# Skaarhoj_VU_board_with_LEDs.net
KiCad netlist of a schematic drawn in EAGLE
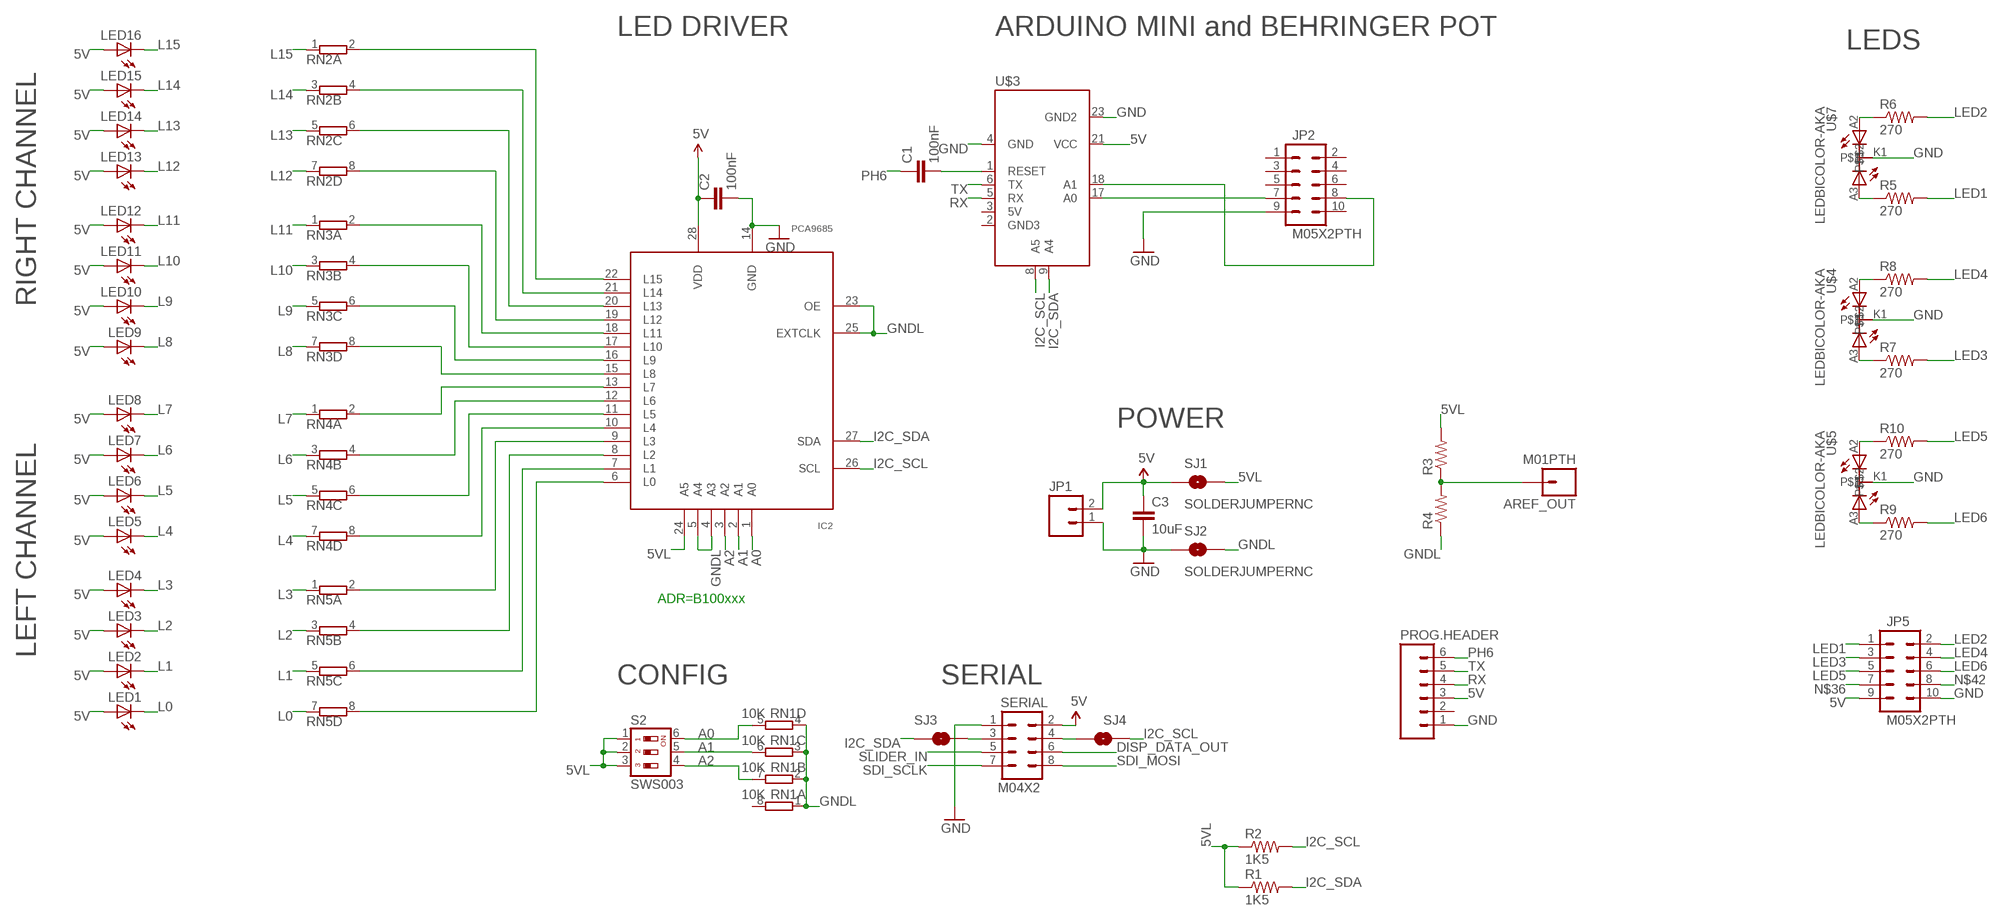
[diagram p0: schematic, sheet 1]

(export (version "E")
  (design (tool "Eeschema 10.0.6"))
  (components
    (comp (ref "AREF_OUT")
      (value "M01PTH")
      (footprint "eagle-import:1X01")
      (libsource (lib "eagle-import") (part "M01PTH"))
    )
    (comp (ref "C1")
      (value "100nF")
      (footprint "eagle-import:0603-CAP")
      (libsource (lib "eagle-import") (part "CAP0603-CAP"))
    )
    (comp (ref "C2")
      (value "100nF")
      (footprint "eagle-import:0603-CAP")
      (libsource (lib "eagle-import") (part "CAP0603-CAP"))
    )
    (comp (ref "C3")
      (value "10uF")
      (footprint "eagle-import:0805")
      (libsource (lib "eagle-import") (part "CAP0805"))
    )
    (comp (ref "IC2")
      (value "PCA9685")
      (footprint "eagle-import:TSSOP28")
      (libsource (lib "eagle-import") (part "PCA9685"))
    )
    (comp (ref "JP1")
      (value "M02PTH")
      (footprint "eagle-import:1X02")
      (libsource (lib "eagle-import") (part "M02PTH"))
    )
    (comp (ref "JP2")
      (value "M05X2PTH")
      (footprint "eagle-import:AVR_ICSP")
      (libsource (lib "eagle-import") (part "M05X2PTH"))
    )
    (comp (ref "JP5")
      (value "M05X2PTH")
      (footprint "eagle-import:AVR_ICSP")
      (libsource (lib "eagle-import") (part "M05X2PTH"))
    )
    (comp (ref "LED1")
      (value "LED3MM")
      (footprint "eagle-import:LED3MM")
      (libsource (lib "eagle-import") (part "LED3MM"))
    )
    (comp (ref "LED2")
      (value "LED3MM")
      (footprint "eagle-import:LED3MM")
      (libsource (lib "eagle-import") (part "LED3MM"))
    )
    (comp (ref "LED3")
      (value "LED3MM")
      (footprint "eagle-import:LED3MM")
      (libsource (lib "eagle-import") (part "LED3MM"))
    )
    (comp (ref "LED4")
      (value "LED3MM")
      (footprint "eagle-import:LED3MM")
      (libsource (lib "eagle-import") (part "LED3MM"))
    )
    (comp (ref "LED5")
      (value "LED3MM")
      (footprint "eagle-import:LED3MM")
      (libsource (lib "eagle-import") (part "LED3MM"))
    )
    (comp (ref "LED6")
      (value "LED3MM")
      (footprint "eagle-import:LED3MM")
      (libsource (lib "eagle-import") (part "LED3MM"))
    )
    (comp (ref "LED7")
      (value "LED3MM")
      (footprint "eagle-import:LED3MM")
      (libsource (lib "eagle-import") (part "LED3MM"))
    )
    (comp (ref "LED8")
      (value "LED3MM")
      (footprint "eagle-import:LED3MM")
      (libsource (lib "eagle-import") (part "LED3MM"))
    )
    (comp (ref "LED9")
      (value "LED3MM")
      (footprint "eagle-import:LED3MM")
      (libsource (lib "eagle-import") (part "LED3MM"))
    )
    (comp (ref "LED10")
      (value "LED3MM")
      (footprint "eagle-import:LED3MM")
      (libsource (lib "eagle-import") (part "LED3MM"))
    )
    (comp (ref "LED11")
      (value "LED3MM")
      (footprint "eagle-import:LED3MM")
      (libsource (lib "eagle-import") (part "LED3MM"))
    )
    (comp (ref "LED12")
      (value "LED3MM")
      (footprint "eagle-import:LED3MM")
      (libsource (lib "eagle-import") (part "LED3MM"))
    )
    (comp (ref "LED13")
      (value "LED3MM")
      (footprint "eagle-import:LED3MM")
      (libsource (lib "eagle-import") (part "LED3MM"))
    )
    (comp (ref "LED14")
      (value "LED3MM")
      (footprint "eagle-import:LED3MM")
      (libsource (lib "eagle-import") (part "LED3MM"))
    )
    (comp (ref "LED15")
      (value "LED3MM")
      (footprint "eagle-import:LED3MM")
      (libsource (lib "eagle-import") (part "LED3MM"))
    )
    (comp (ref "LED16")
      (value "LED3MM")
      (footprint "eagle-import:LED3MM")
      (libsource (lib "eagle-import") (part "LED3MM"))
    )
    (comp (ref "PROG.HEADER")
      (value "M06LOCK")
      (footprint "eagle-import:1X06_LOCK")
      (libsource (lib "eagle-import") (part "M06LOCK"))
    )
    (comp (ref "R1")
      (value "1K5")
      (footprint "eagle-import:0603-RES")
      (libsource (lib "eagle-import") (part "RESISTOR0603-RES"))
    )
    (comp (ref "R2")
      (value "1K5")
      (footprint "eagle-import:0603-RES")
      (libsource (lib "eagle-import") (part "RESISTOR0603-RES"))
    )
    (comp (ref "R3")
      (value "RESISTOR0603-RES")
      (footprint "eagle-import:0603-RES")
      (libsource (lib "eagle-import") (part "RESISTOR0603-RES"))
    )
    (comp (ref "R4")
      (value "RESISTOR0603-RES")
      (footprint "eagle-import:0603-RES")
      (libsource (lib "eagle-import") (part "RESISTOR0603-RES"))
    )
    (comp (ref "R5")
      (value "270")
      (footprint "eagle-import:0603-RES")
      (libsource (lib "eagle-import") (part "RESISTOR0603-RES"))
    )
    (comp (ref "R6")
      (value "270")
      (footprint "eagle-import:0603-RES")
      (libsource (lib "eagle-import") (part "RESISTOR0603-RES"))
    )
    (comp (ref "R7")
      (value "270")
      (footprint "eagle-import:0603-RES")
      (libsource (lib "eagle-import") (part "RESISTOR0603-RES"))
    )
    (comp (ref "R8")
      (value "270")
      (footprint "eagle-import:0603-RES")
      (libsource (lib "eagle-import") (part "RESISTOR0603-RES"))
    )
    (comp (ref "R9")
      (value "270")
      (footprint "eagle-import:0603-RES")
      (libsource (lib "eagle-import") (part "RESISTOR0603-RES"))
    )
    (comp (ref "R10")
      (value "270")
      (footprint "eagle-import:0603-RES")
      (libsource (lib "eagle-import") (part "RESISTOR0603-RES"))
    )
    (comp (ref "RN1")
      (value "10K")
      (footprint "eagle-import:CAY16_HAND")
      (libsource (lib "eagle-import") (part "4R-NCAY16"))
    )
    (comp (ref "RN2")
      (value "E4R")
      (footprint "eagle-import:SIL8")
      (libsource (lib "eagle-import") (part "E4R"))
    )
    (comp (ref "RN3")
      (value "E4R")
      (footprint "eagle-import:SIL8")
      (libsource (lib "eagle-import") (part "E4R"))
    )
    (comp (ref "RN4")
      (value "E4R")
      (footprint "eagle-import:SIL8")
      (libsource (lib "eagle-import") (part "E4R"))
    )
    (comp (ref "RN5")
      (value "E4R")
      (footprint "eagle-import:SIL8")
      (libsource (lib "eagle-import") (part "E4R"))
    )
    (comp (ref "S2")
      (value "SWS003")
      (footprint "eagle-import:SMS-003")
      (libsource (lib "eagle-import") (part "SWS003"))
    )
    (comp (ref "SERIAL")
      (value "M04X2")
      (footprint "eagle-import:2X4")
      (libsource (lib "eagle-import") (part "M04X2"))
    )
    (comp (ref "SJ1")
      (value "SOLDERJUMPERNC")
      (footprint "eagle-import:SJ_2S")
      (libsource (lib "eagle-import") (part "SOLDERJUMPERNC"))
    )
    (comp (ref "SJ2")
      (value "SOLDERJUMPERNC")
      (footprint "eagle-import:SJ_2S")
      (libsource (lib "eagle-import") (part "SOLDERJUMPERNC"))
    )
    (comp (ref "SJ3")
      (value "SOLDERJUMPERNC")
      (footprint "eagle-import:SJ_2S")
      (libsource (lib "eagle-import") (part "SOLDERJUMPERNC"))
    )
    (comp (ref "SJ4")
      (value "SOLDERJUMPERNC")
      (footprint "eagle-import:SJ_2S")
      (libsource (lib "eagle-import") (part "SOLDERJUMPERNC"))
    )
    (comp (ref "U$3")
      (value "ARDUINO_MINI_SE1")
      (footprint "eagle-import:ARDUINO_MINI_SE1")
      (libsource (lib "eagle-import") (part "ARDUINO_MINI_SE1"))
    )
    (comp (ref "U$4")
      (value "LEDBICOLOR-AKA")
      (footprint "eagle-import:LED5MM-BICOLOR")
      (libsource (lib "eagle-import") (part "LEDBICOLOR-AKA"))
    )
    (comp (ref "U$5")
      (value "LEDBICOLOR-AKA")
      (footprint "eagle-import:LED5MM-BICOLOR")
      (libsource (lib "eagle-import") (part "LEDBICOLOR-AKA"))
    )
    (comp (ref "U$7")
      (value "LEDBICOLOR-AKA")
      (footprint "eagle-import:LED5MM-BICOLOR")
      (libsource (lib "eagle-import") (part "LEDBICOLOR-AKA"))
    )
  )
  (nets
    (net (code "1") (name "/5VL") (class "Default")
      (node (ref "IC2") (pin "24") (pinfunction "A5_24") (pintype "input"))
      (node (ref "R1") (pin "1") (pinfunction "1_1") (pintype "passive"))
      (node (ref "R2") (pin "1") (pinfunction "1_1") (pintype "passive"))
      (node (ref "R3") (pin "2") (pinfunction "2_2") (pintype "passive"))
      (node (ref "S2") (pin "1") (pinfunction "1_1") (pintype "passive"))
      (node (ref "S2") (pin "2") (pinfunction "2_2") (pintype "passive"))
      (node (ref "S2") (pin "3") (pinfunction "3_3") (pintype "passive"))
      (node (ref "SJ1") (pin "2") (pinfunction "2_2") (pintype "passive"))
    )
    (net (code "2") (name "/A0") (class "Default")
      (node (ref "IC2") (pin "1") (pinfunction "A0_1") (pintype "input"))
      (node (ref "RN1") (pin "5") (pinfunction "2_5") (pintype "passive"))
      (node (ref "S2") (pin "6") (pinfunction "6_6") (pintype "passive"))
    )
    (net (code "3") (name "/A1") (class "Default")
      (node (ref "IC2") (pin "2") (pinfunction "A1_2") (pintype "input"))
      (node (ref "RN1") (pin "6") (pinfunction "2_6") (pintype "passive"))
      (node (ref "S2") (pin "5") (pinfunction "5_5") (pintype "passive"))
    )
    (net (code "4") (name "/A2") (class "Default")
      (node (ref "IC2") (pin "3") (pinfunction "A2_3") (pintype "input"))
      (node (ref "RN1") (pin "7") (pinfunction "2_7") (pintype "passive"))
      (node (ref "S2") (pin "4") (pinfunction "4_4") (pintype "passive"))
    )
    (net (code "5") (name "/DISP_DATA_OUT") (class "Default")
      (node (ref "SERIAL") (pin "6") (pinfunction "6_6") (pintype "passive"))
    )
    (net (code "6") (name "/GNDL") (class "Default")
      (node (ref "IC2") (pin "23") (pinfunction "OE_23") (pintype "input"))
      (node (ref "IC2") (pin "25") (pinfunction "EXTCLK_25") (pintype "input"))
      (node (ref "IC2") (pin "4") (pinfunction "A3_4") (pintype "input"))
      (node (ref "IC2") (pin "5") (pinfunction "A4_5") (pintype "input"))
      (node (ref "R4") (pin "1") (pinfunction "1_1") (pintype "passive"))
      (node (ref "RN1") (pin "1") (pinfunction "1_1") (pintype "passive"))
      (node (ref "RN1") (pin "2") (pinfunction "1_2") (pintype "passive"))
      (node (ref "RN1") (pin "3") (pinfunction "1_3") (pintype "passive"))
      (node (ref "RN1") (pin "4") (pinfunction "1_4") (pintype "passive"))
      (node (ref "SJ2") (pin "2") (pinfunction "2_2") (pintype "passive"))
    )
    (net (code "7") (name "/I2C_SCL") (class "Default")
      (node (ref "IC2") (pin "26") (pinfunction "SCL_26") (pintype "input"))
      (node (ref "R2") (pin "2") (pinfunction "2_2") (pintype "passive"))
      (node (ref "SJ4") (pin "2") (pinfunction "2_2") (pintype "passive"))
      (node (ref "U$3") (pin "8") (pinfunction "A5_8") (pintype "bidirectional"))
    )
    (net (code "8") (name "/I2C_SDA") (class "Default")
      (node (ref "IC2") (pin "27") (pinfunction "SDA_27") (pintype "input"))
      (node (ref "R1") (pin "2") (pinfunction "2_2") (pintype "passive"))
      (node (ref "SJ3") (pin "1") (pinfunction "1_1") (pintype "passive"))
      (node (ref "U$3") (pin "9") (pinfunction "A4_9") (pintype "bidirectional"))
    )
    (net (code "9") (name "/L0") (class "Default")
      (node (ref "LED1") (pin "K") (pinfunction "C_K") (pintype "passive"))
      (node (ref "RN5") (pin "7") (pinfunction "1_7") (pintype "passive"))
    )
    (net (code "10") (name "/L1") (class "Default")
      (node (ref "LED2") (pin "K") (pinfunction "C_K") (pintype "passive"))
      (node (ref "RN5") (pin "5") (pinfunction "1_5") (pintype "passive"))
    )
    (net (code "11") (name "/L2") (class "Default")
      (node (ref "LED3") (pin "K") (pinfunction "C_K") (pintype "passive"))
      (node (ref "RN5") (pin "3") (pinfunction "1_3") (pintype "passive"))
    )
    (net (code "12") (name "/L3") (class "Default")
      (node (ref "LED4") (pin "K") (pinfunction "C_K") (pintype "passive"))
      (node (ref "RN5") (pin "1") (pinfunction "1_1") (pintype "passive"))
    )
    (net (code "13") (name "/L4") (class "Default")
      (node (ref "LED5") (pin "K") (pinfunction "C_K") (pintype "passive"))
      (node (ref "RN4") (pin "7") (pinfunction "1_7") (pintype "passive"))
    )
    (net (code "14") (name "/L5") (class "Default")
      (node (ref "LED6") (pin "K") (pinfunction "C_K") (pintype "passive"))
      (node (ref "RN4") (pin "5") (pinfunction "1_5") (pintype "passive"))
    )
    (net (code "15") (name "/L6") (class "Default")
      (node (ref "LED7") (pin "K") (pinfunction "C_K") (pintype "passive"))
      (node (ref "RN4") (pin "3") (pinfunction "1_3") (pintype "passive"))
    )
    (net (code "16") (name "/L7") (class "Default")
      (node (ref "LED8") (pin "K") (pinfunction "C_K") (pintype "passive"))
      (node (ref "RN4") (pin "1") (pinfunction "1_1") (pintype "passive"))
    )
    (net (code "17") (name "/L8") (class "Default")
      (node (ref "LED9") (pin "K") (pinfunction "C_K") (pintype "passive"))
      (node (ref "RN3") (pin "7") (pinfunction "1_7") (pintype "passive"))
    )
    (net (code "18") (name "/L9") (class "Default")
      (node (ref "LED10") (pin "K") (pinfunction "C_K") (pintype "passive"))
      (node (ref "RN3") (pin "5") (pinfunction "1_5") (pintype "passive"))
    )
    (net (code "19") (name "/L10") (class "Default")
      (node (ref "LED11") (pin "K") (pinfunction "C_K") (pintype "passive"))
      (node (ref "RN3") (pin "3") (pinfunction "1_3") (pintype "passive"))
    )
    (net (code "20") (name "/L11") (class "Default")
      (node (ref "LED12") (pin "K") (pinfunction "C_K") (pintype "passive"))
      (node (ref "RN3") (pin "1") (pinfunction "1_1") (pintype "passive"))
    )
    (net (code "21") (name "/L12") (class "Default")
      (node (ref "LED13") (pin "K") (pinfunction "C_K") (pintype "passive"))
      (node (ref "RN2") (pin "7") (pinfunction "1_7") (pintype "passive"))
    )
    (net (code "22") (name "/L13") (class "Default")
      (node (ref "LED14") (pin "K") (pinfunction "C_K") (pintype "passive"))
      (node (ref "RN2") (pin "5") (pinfunction "1_5") (pintype "passive"))
    )
    (net (code "23") (name "/L14") (class "Default")
      (node (ref "LED15") (pin "K") (pinfunction "C_K") (pintype "passive"))
      (node (ref "RN2") (pin "3") (pinfunction "1_3") (pintype "passive"))
    )
    (net (code "24") (name "/L15") (class "Default")
      (node (ref "LED16") (pin "K") (pinfunction "C_K") (pintype "passive"))
      (node (ref "RN2") (pin "1") (pinfunction "1_1") (pintype "passive"))
    )
    (net (code "25") (name "/LED1") (class "Default")
      (node (ref "JP5") (pin "1") (pinfunction "1_1") (pintype "passive"))
      (node (ref "R5") (pin "2") (pinfunction "2_2") (pintype "passive"))
    )
    (net (code "26") (name "/LED2") (class "Default")
      (node (ref "JP5") (pin "2") (pinfunction "2_2") (pintype "passive"))
      (node (ref "R6") (pin "2") (pinfunction "2_2") (pintype "passive"))
    )
    (net (code "27") (name "/LED3") (class "Default")
      (node (ref "JP5") (pin "3") (pinfunction "3_3") (pintype "passive"))
      (node (ref "R7") (pin "2") (pinfunction "2_2") (pintype "passive"))
    )
    (net (code "28") (name "/LED4") (class "Default")
      (node (ref "JP5") (pin "4") (pinfunction "4_4") (pintype "passive"))
      (node (ref "R8") (pin "2") (pinfunction "2_2") (pintype "passive"))
    )
    (net (code "29") (name "/LED5") (class "Default")
      (node (ref "JP5") (pin "5") (pinfunction "5_5") (pintype "passive"))
      (node (ref "R10") (pin "2") (pinfunction "2_2") (pintype "passive"))
    )
    (net (code "30") (name "/LED6") (class "Default")
      (node (ref "JP5") (pin "6") (pinfunction "6_6") (pintype "passive"))
      (node (ref "R9") (pin "2") (pinfunction "2_2") (pintype "passive"))
    )
    (net (code "31") (name "/N$36") (class "Default")
      (node (ref "JP5") (pin "7") (pinfunction "7_7") (pintype "passive"))
    )
    (net (code "32") (name "/N$42") (class "Default")
      (node (ref "JP5") (pin "8") (pinfunction "8_8") (pintype "passive"))
    )
    (net (code "33") (name "/PH6") (class "Default")
      (node (ref "C1") (pin "1") (pinfunction "1_1") (pintype "passive"))
      (node (ref "PROG.HEADER") (pin "6") (pinfunction "6_6") (pintype "passive"))
    )
    (net (code "34") (name "/RX") (class "Default")
      (node (ref "PROG.HEADER") (pin "4") (pinfunction "4_4") (pintype "passive"))
      (node (ref "U$3") (pin "5") (pinfunction "RX_5") (pintype "bidirectional"))
    )
    (net (code "35") (name "/SDI_MOSI") (class "Default")
      (node (ref "SERIAL") (pin "8") (pinfunction "8_8") (pintype "passive"))
    )
    (net (code "36") (name "/SDI_SCLK") (class "Default")
      (node (ref "SERIAL") (pin "7") (pinfunction "7_7") (pintype "passive"))
    )
    (net (code "37") (name "/SLIDER_IN") (class "Default")
      (node (ref "SERIAL") (pin "5") (pinfunction "5_5") (pintype "passive"))
    )
    (net (code "38") (name "/TX") (class "Default")
      (node (ref "PROG.HEADER") (pin "5") (pinfunction "5_5") (pintype "passive"))
      (node (ref "U$3") (pin "6") (pinfunction "TX_6") (pintype "bidirectional"))
    )
    (net (code "39") (name "5V") (class "Default")
      (node (ref "C2") (pin "1") (pinfunction "1_1") (pintype "passive"))
      (node (ref "C3") (pin "1") (pinfunction "1_1") (pintype "passive"))
      (node (ref "IC2") (pin "28") (pinfunction "VDD_28") (pintype "power_in"))
      (node (ref "JP1") (pin "2") (pinfunction "2_2") (pintype "passive"))
      (node (ref "JP5") (pin "9") (pinfunction "9_9") (pintype "passive"))
      (node (ref "LED1") (pin "A") (pinfunction "A_A") (pintype "passive"))
      (node (ref "LED10") (pin "A") (pinfunction "A_A") (pintype "passive"))
      (node (ref "LED11") (pin "A") (pinfunction "A_A") (pintype "passive"))
      (node (ref "LED12") (pin "A") (pinfunction "A_A") (pintype "passive"))
      (node (ref "LED13") (pin "A") (pinfunction "A_A") (pintype "passive"))
      (node (ref "LED14") (pin "A") (pinfunction "A_A") (pintype "passive"))
      (node (ref "LED15") (pin "A") (pinfunction "A_A") (pintype "passive"))
      (node (ref "LED16") (pin "A") (pinfunction "A_A") (pintype "passive"))
      (node (ref "LED2") (pin "A") (pinfunction "A_A") (pintype "passive"))
      (node (ref "LED3") (pin "A") (pinfunction "A_A") (pintype "passive"))
      (node (ref "LED4") (pin "A") (pinfunction "A_A") (pintype "passive"))
      (node (ref "LED5") (pin "A") (pinfunction "A_A") (pintype "passive"))
      (node (ref "LED6") (pin "A") (pinfunction "A_A") (pintype "passive"))
      (node (ref "LED7") (pin "A") (pinfunction "A_A") (pintype "passive"))
      (node (ref "LED8") (pin "A") (pinfunction "A_A") (pintype "passive"))
      (node (ref "LED9") (pin "A") (pinfunction "A_A") (pintype "passive"))
      (node (ref "PROG.HEADER") (pin "3") (pinfunction "3_3") (pintype "passive"))
      (node (ref "SERIAL") (pin "2") (pinfunction "2_2") (pintype "passive"))
      (node (ref "SJ1") (pin "1") (pinfunction "1_1") (pintype "passive"))
      (node (ref "U$3") (pin "21") (pinfunction "VCC_21") (pintype "bidirectional"))
    )
    (net (code "40") (name "GND") (class "Default")
      (node (ref "C2") (pin "2") (pinfunction "2_2") (pintype "passive"))
      (node (ref "C3") (pin "2") (pinfunction "2_2") (pintype "passive"))
      (node (ref "IC2") (pin "14") (pinfunction "GND_14") (pintype "power_in"))
      (node (ref "JP1") (pin "1") (pinfunction "1_1") (pintype "passive"))
      (node (ref "JP2") (pin "9") (pinfunction "9_9") (pintype "passive"))
      (node (ref "JP5") (pin "10") (pinfunction "10_10") (pintype "passive"))
      (node (ref "PROG.HEADER") (pin "1") (pinfunction "1_1") (pintype "passive"))
      (node (ref "SERIAL") (pin "1") (pinfunction "1_1") (pintype "passive"))
      (node (ref "SJ2") (pin "1") (pinfunction "1_1") (pintype "passive"))
      (node (ref "U$3") (pin "23") (pinfunction "GND2_23") (pintype "bidirectional"))
      (node (ref "U$3") (pin "4") (pinfunction "GND_4") (pintype "bidirectional"))
      (node (ref "U$4") (pin "K1") (pinfunction "P$1_K1") (pintype "bidirectional"))
      (node (ref "U$5") (pin "K1") (pinfunction "P$1_K1") (pintype "bidirectional"))
      (node (ref "U$7") (pin "K1") (pinfunction "P$1_K1") (pintype "bidirectional"))
    )
    (net (code "41") (name "Net-(AREF_OUT-Pad1)") (class "Default")
      (node (ref "AREF_OUT") (pin "1") (pinfunction "1_1") (pintype "passive"))
      (node (ref "R3") (pin "1") (pinfunction "1_1") (pintype "passive"))
      (node (ref "R4") (pin "2") (pinfunction "2_2") (pintype "passive"))
    )
    (net (code "42") (name "Net-(IC2-L0)") (class "Default")
      (node (ref "IC2") (pin "6") (pinfunction "L0_6") (pintype "output"))
      (node (ref "RN5") (pin "8") (pinfunction "2_8") (pintype "passive"))
    )
    (net (code "43") (name "Net-(IC2-L1)") (class "Default")
      (node (ref "IC2") (pin "7") (pinfunction "L1_7") (pintype "output"))
      (node (ref "RN5") (pin "6") (pinfunction "2_6") (pintype "passive"))
    )
    (net (code "44") (name "Net-(IC2-L2)") (class "Default")
      (node (ref "IC2") (pin "8") (pinfunction "L2_8") (pintype "output"))
      (node (ref "RN5") (pin "4") (pinfunction "2_4") (pintype "passive"))
    )
    (net (code "45") (name "Net-(IC2-L3)") (class "Default")
      (node (ref "IC2") (pin "9") (pinfunction "L3_9") (pintype "output"))
      (node (ref "RN5") (pin "2") (pinfunction "2_2") (pintype "passive"))
    )
    (net (code "46") (name "Net-(IC2-L4)") (class "Default")
      (node (ref "IC2") (pin "10") (pinfunction "L4_10") (pintype "output"))
      (node (ref "RN4") (pin "8") (pinfunction "2_8") (pintype "passive"))
    )
    (net (code "47") (name "Net-(IC2-L5)") (class "Default")
      (node (ref "IC2") (pin "11") (pinfunction "L5_11") (pintype "output"))
      (node (ref "RN4") (pin "6") (pinfunction "2_6") (pintype "passive"))
    )
    (net (code "48") (name "Net-(IC2-L6)") (class "Default")
      (node (ref "IC2") (pin "12") (pinfunction "L6_12") (pintype "output"))
      (node (ref "RN4") (pin "4") (pinfunction "2_4") (pintype "passive"))
    )
    (net (code "49") (name "Net-(IC2-L7)") (class "Default")
      (node (ref "IC2") (pin "13") (pinfunction "L7_13") (pintype "output"))
      (node (ref "RN4") (pin "2") (pinfunction "2_2") (pintype "passive"))
    )
    (net (code "50") (name "Net-(IC2-L8)") (class "Default")
      (node (ref "IC2") (pin "15") (pinfunction "L8_15") (pintype "output"))
      (node (ref "RN3") (pin "8") (pinfunction "2_8") (pintype "passive"))
    )
    (net (code "51") (name "Net-(IC2-L9)") (class "Default")
      (node (ref "IC2") (pin "16") (pinfunction "L9_16") (pintype "output"))
      (node (ref "RN3") (pin "6") (pinfunction "2_6") (pintype "passive"))
    )
    (net (code "52") (name "Net-(IC2-L10)") (class "Default")
      (node (ref "IC2") (pin "17") (pinfunction "L10_17") (pintype "output"))
      (node (ref "RN3") (pin "4") (pinfunction "2_4") (pintype "passive"))
    )
    (net (code "53") (name "Net-(IC2-L11)") (class "Default")
      (node (ref "IC2") (pin "18") (pinfunction "L11_18") (pintype "output"))
      (node (ref "RN3") (pin "2") (pinfunction "2_2") (pintype "passive"))
    )
    (net (code "54") (name "Net-(IC2-L12)") (class "Default")
      (node (ref "IC2") (pin "19") (pinfunction "L12_19") (pintype "output"))
      (node (ref "RN2") (pin "8") (pinfunction "2_8") (pintype "passive"))
    )
    (net (code "55") (name "Net-(IC2-L13)") (class "Default")
      (node (ref "IC2") (pin "20") (pinfunction "L13_20") (pintype "output"))
      (node (ref "RN2") (pin "6") (pinfunction "2_6") (pintype "passive"))
    )
    (net (code "56") (name "Net-(IC2-L14)") (class "Default")
      (node (ref "IC2") (pin "21") (pinfunction "L14_21") (pintype "output"))
      (node (ref "RN2") (pin "4") (pinfunction "2_4") (pintype "passive"))
    )
    (net (code "57") (name "Net-(IC2-L15)") (class "Default")
      (node (ref "IC2") (pin "22") (pinfunction "L15_22") (pintype "output"))
      (node (ref "RN2") (pin "2") (pinfunction "2_2") (pintype "passive"))
    )
    (net (code "58") (name "Net-(SERIAL-Pad3)") (class "Default")
      (node (ref "SERIAL") (pin "3") (pinfunction "3_3") (pintype "passive"))
      (node (ref "SJ3") (pin "2") (pinfunction "2_2") (pintype "passive"))
    )
    (net (code "59") (name "Net-(SERIAL-Pad4)") (class "Default")
      (node (ref "SERIAL") (pin "4") (pinfunction "4_4") (pintype "passive"))
      (node (ref "SJ4") (pin "1") (pinfunction "1_1") (pintype "passive"))
    )
    (net (code "60") (name "Net-(U$3-A0)") (class "Default")
      (node (ref "JP2") (pin "7") (pinfunction "7_7") (pintype "passive"))
      (node (ref "U$3") (pin "17") (pinfunction "A0_17") (pintype "bidirectional"))
    )
    (net (code "61") (name "Net-(U$3-A1)") (class "Default")
      (node (ref "JP2") (pin "8") (pinfunction "8_8") (pintype "passive"))
      (node (ref "U$3") (pin "18") (pinfunction "A1_18") (pintype "bidirectional"))
    )
    (net (code "62") (name "Net-(U$3-RESET)") (class "Default")
      (node (ref "C1") (pin "2") (pinfunction "2_2") (pintype "passive"))
      (node (ref "U$3") (pin "1") (pinfunction "RESET_1") (pintype "bidirectional"))
    )
    (net (code "63") (name "Net-(U$4-P$2)") (class "Default")
      (node (ref "R8") (pin "1") (pinfunction "1_1") (pintype "passive"))
      (node (ref "U$4") (pin "A2") (pinfunction "P$2_A2") (pintype "bidirectional"))
    )
    (net (code "64") (name "Net-(U$4-P$3)") (class "Default")
      (node (ref "R7") (pin "1") (pinfunction "1_1") (pintype "passive"))
      (node (ref "U$4") (pin "A3") (pinfunction "P$3_A3") (pintype "bidirectional"))
    )
    (net (code "65") (name "Net-(U$5-P$2)") (class "Default")
      (node (ref "R10") (pin "1") (pinfunction "1_1") (pintype "passive"))
      (node (ref "U$5") (pin "A2") (pinfunction "P$2_A2") (pintype "bidirectional"))
    )
    (net (code "66") (name "Net-(U$5-P$3)") (class "Default")
      (node (ref "R9") (pin "1") (pinfunction "1_1") (pintype "passive"))
      (node (ref "U$5") (pin "A3") (pinfunction "P$3_A3") (pintype "bidirectional"))
    )
    (net (code "67") (name "Net-(U$7-P$2)") (class "Default")
      (node (ref "R6") (pin "1") (pinfunction "1_1") (pintype "passive"))
      (node (ref "U$7") (pin "A2") (pinfunction "P$2_A2") (pintype "bidirectional"))
    )
    (net (code "68") (name "Net-(U$7-P$3)") (class "Default")
      (node (ref "R5") (pin "1") (pinfunction "1_1") (pintype "passive"))
      (node (ref "U$7") (pin "A3") (pinfunction "P$3_A3") (pintype "bidirectional"))
    )
    (net (code "69") (name "unconnected-(JP2-Pad1)") (class "Default")
      (node (ref "JP2") (pin "1") (pinfunction "1_1") (pintype "passive"))
    )
    (net (code "70") (name "unconnected-(JP2-Pad2)") (class "Default")
      (node (ref "JP2") (pin "2") (pinfunction "2_2") (pintype "passive"))
    )
    (net (code "71") (name "unconnected-(JP2-Pad3)") (class "Default")
      (node (ref "JP2") (pin "3") (pinfunction "3_3") (pintype "passive"))
    )
    (net (code "72") (name "unconnected-(JP2-Pad4)") (class "Default")
      (node (ref "JP2") (pin "4") (pinfunction "4_4") (pintype "passive"))
    )
    (net (code "73") (name "unconnected-(JP2-Pad5)") (class "Default")
      (node (ref "JP2") (pin "5") (pinfunction "5_5") (pintype "passive"))
    )
    (net (code "74") (name "unconnected-(JP2-Pad6)") (class "Default")
      (node (ref "JP2") (pin "6") (pinfunction "6_6") (pintype "passive"))
    )
    (net (code "75") (name "unconnected-(JP2-Pad10)") (class "Default")
      (node (ref "JP2") (pin "10") (pinfunction "10_10") (pintype "passive"))
    )
    (net (code "76") (name "unconnected-(PROG.HEADER-Pad2)") (class "Default")
      (node (ref "PROG.HEADER") (pin "2") (pinfunction "2_2") (pintype "passive"))
    )
    (net (code "77") (name "unconnected-(RN1A-2-Pad8)") (class "Default")
      (node (ref "RN1") (pin "8") (pinfunction "2_8") (pintype "passive"))
    )
    (net (code "78") (name "unconnected-(U$3-5V-Pad3)") (class "Default")
      (node (ref "U$3") (pin "3") (pinfunction "5V_3") (pintype "bidirectional"))
    )
    (net (code "79") (name "unconnected-(U$3-GND3-Pad2)") (class "Default")
      (node (ref "U$3") (pin "2") (pinfunction "GND3_2") (pintype "bidirectional"))
    )
  )
)
